# testboard.net
KiCad netlist of a schematic drawn in Altium Designer
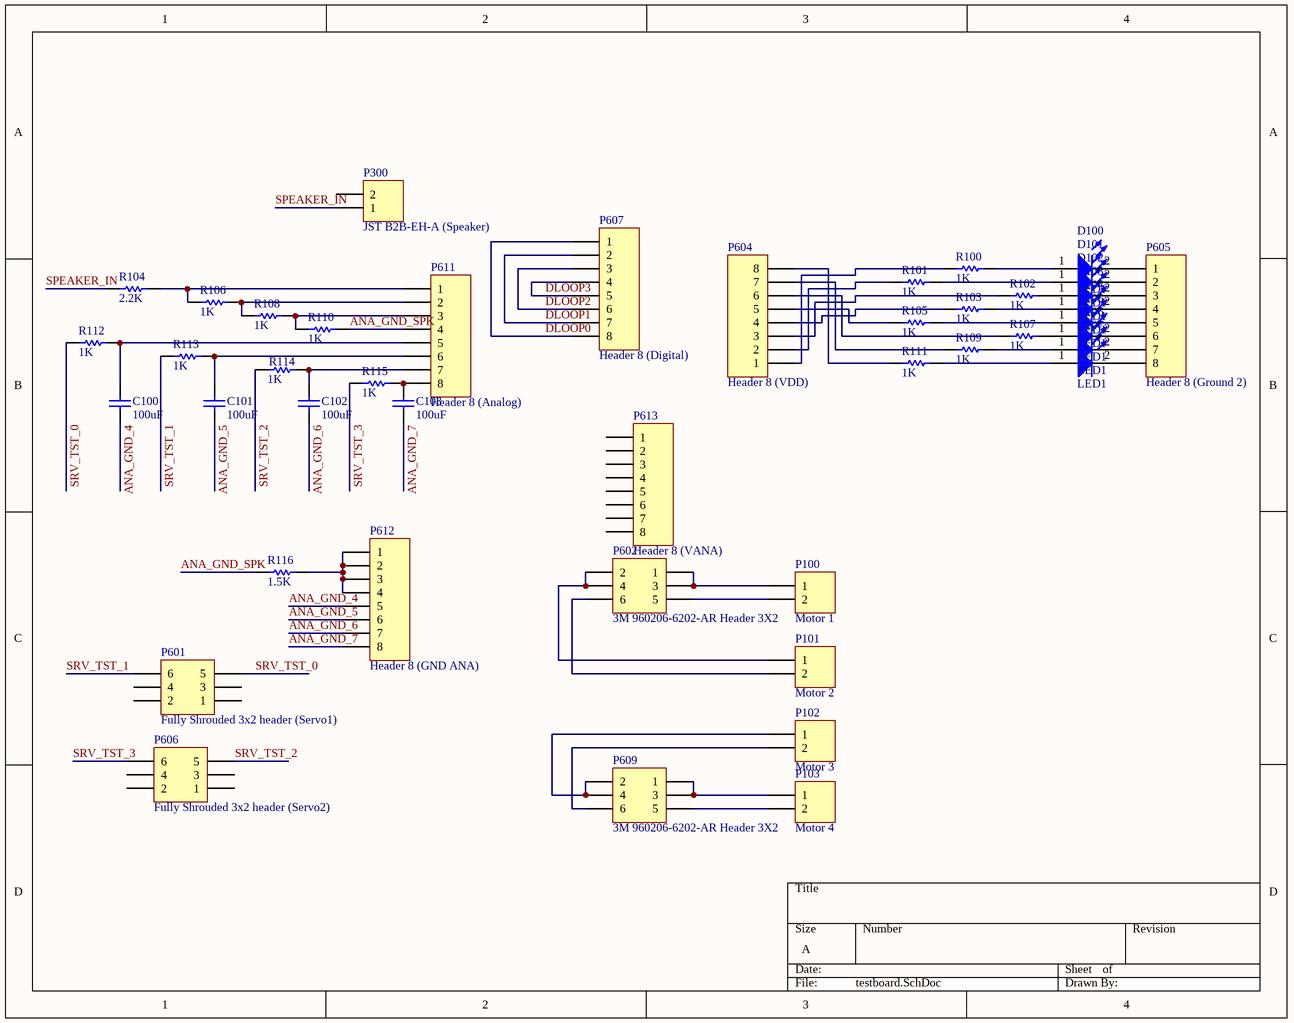
[diagram p0: testboard.SchDoc]

(export (version "E")
  (design (tool "Eeschema 10.0.6"))
  (components
    (comp (ref "C100")
      (value "100uF")
      (footprint "CAPPR5-5x5")
      (description "Capacitor")
      (fields (field (name "PUBLISHER") "Altium Limited"))
      (libsource (lib "Miscellaneous Devices") (part "Cap"))
    )
    (comp (ref "C101")
      (value "100uF")
      (footprint "CAPPR5-5x5")
      (description "Capacitor")
      (fields (field (name "PUBLISHER") "Altium Limited"))
      (libsource (lib "Miscellaneous Devices") (part "Cap"))
    )
    (comp (ref "C102")
      (value "100uF")
      (footprint "CAPPR5-5x5")
      (description "Capacitor")
      (fields (field (name "PUBLISHER") "Altium Limited"))
      (libsource (lib "Miscellaneous Devices") (part "Cap"))
    )
    (comp (ref "C103")
      (value "100uF")
      (footprint "CAPPR5-5x5")
      (description "Capacitor")
      (fields (field (name "PUBLISHER") "Altium Limited"))
      (libsource (lib "Miscellaneous Devices") (part "Cap"))
    )
    (comp (ref "D100")
      (value "LED1")
      (footprint "TLHG520")
      (description "Typical RED GaAs LED")
      (fields (field (name "PUBLISHER") "Altium Limited"))
      (libsource (lib "Miscellaneous Devices") (part "LED1"))
    )
    (comp (ref "D101")
      (value "LED1")
      (footprint "TLHG520")
      (description "Typical RED GaAs LED")
      (fields (field (name "PUBLISHER") "Altium Limited"))
      (libsource (lib "Miscellaneous Devices") (part "LED1"))
    )
    (comp (ref "D102")
      (value "LED1")
      (footprint "TLHG520")
      (description "Typical RED GaAs LED")
      (fields (field (name "PUBLISHER") "Altium Limited"))
      (libsource (lib "Miscellaneous Devices") (part "LED1"))
    )
    (comp (ref "D103")
      (value "LED1")
      (footprint "TLHG520")
      (description "Typical RED GaAs LED")
      (fields (field (name "PUBLISHER") "Altium Limited"))
      (libsource (lib "Miscellaneous Devices") (part "LED1"))
    )
    (comp (ref "D104")
      (value "LED1")
      (footprint "TLHG520")
      (description "Typical RED GaAs LED")
      (fields (field (name "PUBLISHER") "Altium Limited"))
      (libsource (lib "") (part "LED1_1"))
    )
    (comp (ref "D105")
      (value "LED1")
      (footprint "TLHG520")
      (description "Typical RED GaAs LED")
      (fields (field (name "PUBLISHER") "Altium Limited"))
      (libsource (lib "Miscellaneous Devices") (part "LED1"))
    )
    (comp (ref "D106")
      (value "LED1")
      (footprint "TLHG520")
      (description "Typical RED GaAs LED")
      (fields (field (name "PUBLISHER") "Altium Limited"))
      (libsource (lib "Miscellaneous Devices") (part "LED1"))
    )
    (comp (ref "D107")
      (value "LED1")
      (footprint "TLHG520")
      (description "Typical RED GaAs LED")
      (fields (field (name "PUBLISHER") "Altium Limited"))
      (libsource (lib "Miscellaneous Devices") (part "LED1"))
    )
    (comp (ref "P100")
      (value "Motor 1")
      (footprint "weidmuller_1716060000")
      (description "Header, 2-Pin")
      (fields (field (name "PUBLISHER") "Altium Limited"))
      (libsource (lib "") (part "Header 2_1"))
    )
    (comp (ref "P101")
      (value "Motor 2")
      (footprint "weidmuller_1716060000")
      (description "Header, 2-Pin")
      (fields (field (name "PUBLISHER") "Altium Limited"))
      (libsource (lib "") (part "Header 2_1"))
    )
    (comp (ref "P102")
      (value "Motor 3")
      (footprint "weidmuller_1716060000")
      (description "Header, 2-Pin")
      (fields (field (name "PUBLISHER") "Altium Limited"))
      (libsource (lib "") (part "Header 2_1"))
    )
    (comp (ref "P103")
      (value "Motor 4")
      (footprint "weidmuller_1716060000")
      (description "Header, 2-Pin")
      (fields (field (name "PUBLISHER") "Altium Limited"))
      (libsource (lib "") (part "Header 2_1"))
    )
    (comp (ref "P300")
      (value "JST B2B-EH-A (Speaker)")
      (footprint "JST_B2B_EH_A")
      (description "Header, 2-Pin")
      (fields (field (name "PUBLISHER") "Altium Limited"))
      (libsource (lib "Miscellaneous Connectors") (part "Header 2"))
    )
    (comp (ref "P601")
      (value "Fully Shrouded 3x2 header (Servo1)")
      (footprint "HEADER2X3_SHROUDED")
      (description "Header, 3-Pin, Dual row")
      (fields (field (name "PUBLISHER") "Altium Limited"))
      (libsource (lib "") (part "Header 3X2_1"))
    )
    (comp (ref "P602")
      (value "3M 960206-6202-AR Header 3X2")
      (footprint "HDR2X3")
      (description "Header, 3-Pin, Dual row")
      (fields (field (name "PUBLISHER") "Altium Limited"))
      (libsource (lib "Miscellaneous Connectors") (part "Header 3X2"))
    )
    (comp (ref "P604")
      (value "Header 8 (VDD)")
      (footprint "HDR1X8")
      (description "Header, 8-Pin")
      (fields (field (name "PUBLISHER") "Altium Limited"))
      (libsource (lib "") (part "Header 8_1"))
    )
    (comp (ref "P605")
      (value "Header 8 (Ground 2)")
      (footprint "HDR1X8")
      (description "Header, 8-Pin")
      (fields (field (name "PUBLISHER") "Altium Limited"))
      (libsource (lib "Miscellaneous Connectors") (part "Header 8"))
    )
    (comp (ref "P606")
      (value "Fully Shrouded 3x2 header (Servo2)")
      (footprint "HEADER2X3_SHROUDED")
      (description "Header, 3-Pin, Dual row")
      (fields (field (name "PUBLISHER") "Altium Limited"))
      (libsource (lib "") (part "Header 3X2_1"))
    )
    (comp (ref "P607")
      (value "Header 8 (Digital)")
      (footprint "HDR1X8")
      (description "Header, 8-Pin")
      (fields (field (name "PUBLISHER") "Altium Limited"))
      (libsource (lib "Miscellaneous Connectors") (part "Header 8"))
    )
    (comp (ref "P609")
      (value "3M 960206-6202-AR Header 3X2")
      (footprint "HDR2X3")
      (description "Header, 3-Pin, Dual row")
      (fields (field (name "PUBLISHER") "Altium Limited"))
      (libsource (lib "Miscellaneous Connectors") (part "Header 3X2"))
    )
    (comp (ref "P611")
      (value "Header 8 (Analog)")
      (footprint "HDR1X8")
      (description "Header, 8-Pin")
      (fields (field (name "PUBLISHER") "Altium Limited"))
      (libsource (lib "Miscellaneous Connectors") (part "Header 8"))
    )
    (comp (ref "P612")
      (value "Header 8 (GND ANA)")
      (footprint "HDR1X8")
      (description "Header, 8-Pin")
      (fields (field (name "PUBLISHER") "Altium Limited"))
      (libsource (lib "Miscellaneous Connectors") (part "Header 8"))
    )
    (comp (ref "P613")
      (value "Header 8 (VANA)")
      (footprint "HDR1X8")
      (description "Header, 8-Pin")
      (fields (field (name "PUBLISHER") "Altium Limited"))
      (libsource (lib "Miscellaneous Connectors") (part "Header 8"))
    )
    (comp (ref "R100")
      (value "1K")
      (footprint "AXIAL-0.3")
      (description "Resistor")
      (fields (field (name "PUBLISHER") "Altium Limited"))
      (libsource (lib "Miscellaneous Devices") (part "Res1"))
    )
    (comp (ref "R101")
      (value "1K")
      (footprint "AXIAL-0.3")
      (description "Resistor")
      (fields (field (name "PUBLISHER") "Altium Limited"))
      (libsource (lib "Miscellaneous Devices") (part "Res1"))
    )
    (comp (ref "R102")
      (value "1K")
      (footprint "AXIAL-0.3")
      (description "Resistor")
      (fields (field (name "PUBLISHER") "Altium Limited"))
      (libsource (lib "Miscellaneous Devices") (part "Res1"))
    )
    (comp (ref "R103")
      (value "1K")
      (footprint "AXIAL-0.3")
      (description "Resistor")
      (fields (field (name "PUBLISHER") "Altium Limited"))
      (libsource (lib "Miscellaneous Devices") (part "Res1"))
    )
    (comp (ref "R104")
      (value "2.2K")
      (footprint "AXIAL-0.3")
      (description "Resistor")
      (fields (field (name "PUBLISHER") "Altium Limited"))
      (libsource (lib "Miscellaneous Devices") (part "Res1"))
    )
    (comp (ref "R105")
      (value "1K")
      (footprint "AXIAL-0.3")
      (description "Resistor")
      (fields (field (name "PUBLISHER") "Altium Limited"))
      (libsource (lib "Miscellaneous Devices") (part "Res1"))
    )
    (comp (ref "R106")
      (value "1K")
      (footprint "AXIAL-0.3")
      (description "Resistor")
      (fields (field (name "PUBLISHER") "Altium Limited"))
      (libsource (lib "Miscellaneous Devices") (part "Res1"))
    )
    (comp (ref "R107")
      (value "1K")
      (footprint "AXIAL-0.3")
      (description "Resistor")
      (fields (field (name "PUBLISHER") "Altium Limited"))
      (libsource (lib "Miscellaneous Devices") (part "Res1"))
    )
    (comp (ref "R108")
      (value "1K")
      (footprint "AXIAL-0.3")
      (description "Resistor")
      (fields (field (name "PUBLISHER") "Altium Limited"))
      (libsource (lib "Miscellaneous Devices") (part "Res1"))
    )
    (comp (ref "R109")
      (value "1K")
      (footprint "AXIAL-0.3")
      (description "Resistor")
      (fields (field (name "PUBLISHER") "Altium Limited"))
      (libsource (lib "Miscellaneous Devices") (part "Res1"))
    )
    (comp (ref "R110")
      (value "1K")
      (footprint "AXIAL-0.3")
      (description "Resistor")
      (fields (field (name "PUBLISHER") "Altium Limited"))
      (libsource (lib "Miscellaneous Devices") (part "Res1"))
    )
    (comp (ref "R111")
      (value "1K")
      (footprint "AXIAL-0.3")
      (description "Resistor")
      (fields (field (name "PUBLISHER") "Altium Limited"))
      (libsource (lib "Miscellaneous Devices") (part "Res1"))
    )
    (comp (ref "R112")
      (value "1K")
      (footprint "AXIAL-0.3")
      (description "Resistor")
      (fields (field (name "PUBLISHER") "Altium Limited"))
      (libsource (lib "Miscellaneous Devices") (part "Res1"))
    )
    (comp (ref "R113")
      (value "1K")
      (footprint "AXIAL-0.3")
      (description "Resistor")
      (fields (field (name "PUBLISHER") "Altium Limited"))
      (libsource (lib "Miscellaneous Devices") (part "Res1"))
    )
    (comp (ref "R114")
      (value "1K")
      (footprint "AXIAL-0.3")
      (description "Resistor")
      (fields (field (name "PUBLISHER") "Altium Limited"))
      (libsource (lib "Miscellaneous Devices") (part "Res1"))
    )
    (comp (ref "R115")
      (value "1K")
      (footprint "AXIAL-0.3")
      (description "Resistor")
      (fields (field (name "PUBLISHER") "Altium Limited"))
      (libsource (lib "Miscellaneous Devices") (part "Res1"))
    )
    (comp (ref "R116")
      (value "1.5K")
      (footprint "AXIAL-0.3")
      (description "Resistor")
      (fields (field (name "PUBLISHER") "Altium Limited"))
      (libsource (lib "Miscellaneous Devices") (part "Res1"))
    )
  )
  (nets
    (net (code "1") (name "/ANA_GND_4") (class "Default")
      (node (ref "C100") (pin "1") (pinfunction "1_1") (pintype "passive"))
      (node (ref "P612") (pin "5") (pinfunction "5_5") (pintype "passive"))
    )
    (net (code "2") (name "/ANA_GND_5") (class "Default")
      (node (ref "C101") (pin "1") (pinfunction "1_1") (pintype "passive"))
      (node (ref "P612") (pin "6") (pinfunction "6_6") (pintype "passive"))
    )
    (net (code "3") (name "/ANA_GND_6") (class "Default")
      (node (ref "C102") (pin "1") (pinfunction "1_1") (pintype "passive"))
      (node (ref "P612") (pin "7") (pinfunction "7_7") (pintype "passive"))
    )
    (net (code "4") (name "/ANA_GND_7") (class "Default")
      (node (ref "C103") (pin "1") (pinfunction "1_1") (pintype "passive"))
      (node (ref "P612") (pin "8") (pinfunction "8_8") (pintype "passive"))
    )
    (net (code "5") (name "/ANA_GND_SPK") (class "Default")
      (node (ref "P611") (pin "4") (pinfunction "4_4") (pintype "passive"))
      (node (ref "R110") (pin "1") (pinfunction "1_1") (pintype "passive"))
      (node (ref "R116") (pin "1") (pinfunction "1_1") (pintype "passive"))
    )
    (net (code "6") (name "/DLOOP0") (class "Default")
      (node (ref "P607") (pin "1") (pinfunction "1_1") (pintype "passive"))
      (node (ref "P607") (pin "8") (pinfunction "8_8") (pintype "passive"))
    )
    (net (code "7") (name "/DLOOP1") (class "Default")
      (node (ref "P607") (pin "2") (pinfunction "2_2") (pintype "passive"))
      (node (ref "P607") (pin "7") (pinfunction "7_7") (pintype "passive"))
    )
    (net (code "8") (name "/DLOOP2") (class "Default")
      (node (ref "P607") (pin "3") (pinfunction "3_3") (pintype "passive"))
      (node (ref "P607") (pin "6") (pinfunction "6_6") (pintype "passive"))
    )
    (net (code "9") (name "/DLOOP3") (class "Default")
      (node (ref "P607") (pin "4") (pinfunction "4_4") (pintype "passive"))
      (node (ref "P607") (pin "5") (pinfunction "5_5") (pintype "passive"))
    )
    (net (code "10") (name "/SPEAKER_IN") (class "Default")
      (node (ref "P300") (pin "1") (pinfunction "1_1") (pintype "passive"))
      (node (ref "R104") (pin "2") (pinfunction "2_2") (pintype "passive"))
    )
    (net (code "11") (name "/SRV_TST_0") (class "Default")
      (node (ref "P601") (pin "5") (pinfunction "5_5") (pintype "passive"))
      (node (ref "R112") (pin "1") (pinfunction "1_1") (pintype "passive"))
    )
    (net (code "12") (name "/SRV_TST_1") (class "Default")
      (node (ref "P601") (pin "6") (pinfunction "6_6") (pintype "passive"))
      (node (ref "R113") (pin "1") (pinfunction "1_1") (pintype "passive"))
    )
    (net (code "13") (name "/SRV_TST_2") (class "Default")
      (node (ref "P606") (pin "5") (pinfunction "5_5") (pintype "passive"))
      (node (ref "R114") (pin "1") (pinfunction "1_1") (pintype "passive"))
    )
    (net (code "14") (name "/SRV_TST_3") (class "Default")
      (node (ref "P606") (pin "6") (pinfunction "6_6") (pintype "passive"))
      (node (ref "R115") (pin "1") (pinfunction "1_1") (pintype "passive"))
    )
    (net (code "15") (name "Net-(C100-Pad2)") (class "Default")
      (node (ref "C100") (pin "2") (pinfunction "2_2") (pintype "passive"))
      (node (ref "P611") (pin "5") (pinfunction "5_5") (pintype "passive"))
      (node (ref "R112") (pin "2") (pinfunction "2_2") (pintype "passive"))
    )
    (net (code "16") (name "Net-(C101-Pad2)") (class "Default")
      (node (ref "C101") (pin "2") (pinfunction "2_2") (pintype "passive"))
      (node (ref "P611") (pin "6") (pinfunction "6_6") (pintype "passive"))
      (node (ref "R113") (pin "2") (pinfunction "2_2") (pintype "passive"))
    )
    (net (code "17") (name "Net-(C102-Pad2)") (class "Default")
      (node (ref "C102") (pin "2") (pinfunction "2_2") (pintype "passive"))
      (node (ref "P611") (pin "7") (pinfunction "7_7") (pintype "passive"))
      (node (ref "R114") (pin "2") (pinfunction "2_2") (pintype "passive"))
    )
    (net (code "18") (name "Net-(C103-Pad2)") (class "Default")
      (node (ref "C103") (pin "2") (pinfunction "2_2") (pintype "passive"))
      (node (ref "P611") (pin "8") (pinfunction "8_8") (pintype "passive"))
      (node (ref "R115") (pin "2") (pinfunction "2_2") (pintype "passive"))
    )
    (net (code "19") (name "Net-(D100-A)") (class "Default")
      (node (ref "D100") (pin "1") (pinfunction "A_1") (pintype "passive"))
      (node (ref "R100") (pin "1") (pinfunction "1_1") (pintype "passive"))
    )
    (net (code "20") (name "Net-(D100-K)") (class "Default")
      (node (ref "D100") (pin "2") (pinfunction "K_2") (pintype "passive"))
      (node (ref "P605") (pin "1") (pinfunction "1_1") (pintype "passive"))
    )
    (net (code "21") (name "Net-(D101-A)") (class "Default")
      (node (ref "D101") (pin "1") (pinfunction "A_1") (pintype "passive"))
      (node (ref "R101") (pin "1") (pinfunction "1_1") (pintype "passive"))
    )
    (net (code "22") (name "Net-(D101-K)") (class "Default")
      (node (ref "D101") (pin "2") (pinfunction "K_2") (pintype "passive"))
      (node (ref "P605") (pin "2") (pinfunction "2_2") (pintype "passive"))
    )
    (net (code "23") (name "Net-(D102-A)") (class "Default")
      (node (ref "D102") (pin "1") (pinfunction "A_1") (pintype "passive"))
      (node (ref "R102") (pin "1") (pinfunction "1_1") (pintype "passive"))
    )
    (net (code "24") (name "Net-(D102-K)") (class "Default")
      (node (ref "D102") (pin "2") (pinfunction "K_2") (pintype "passive"))
      (node (ref "P605") (pin "3") (pinfunction "3_3") (pintype "passive"))
    )
    (net (code "25") (name "Net-(D103-A)") (class "Default")
      (node (ref "D103") (pin "1") (pinfunction "A_1") (pintype "passive"))
      (node (ref "R103") (pin "1") (pinfunction "1_1") (pintype "passive"))
    )
    (net (code "26") (name "Net-(D103-K)") (class "Default")
      (node (ref "D103") (pin "2") (pinfunction "K_2") (pintype "passive"))
      (node (ref "P605") (pin "4") (pinfunction "4_4") (pintype "passive"))
    )
    (net (code "27") (name "Net-(D104A-A)") (class "Default")
      (node (ref "D104") (pin "1") (pinfunction "A_1") (pintype "passive"))
      (node (ref "R105") (pin "1") (pinfunction "1_1") (pintype "passive"))
    )
    (net (code "28") (name "Net-(D105-A)") (class "Default")
      (node (ref "D105") (pin "1") (pinfunction "A_1") (pintype "passive"))
      (node (ref "R107") (pin "1") (pinfunction "1_1") (pintype "passive"))
    )
    (net (code "29") (name "Net-(D105-K)") (class "Default")
      (node (ref "D105") (pin "2") (pinfunction "K_2") (pintype "passive"))
      (node (ref "P605") (pin "6") (pinfunction "6_6") (pintype "passive"))
    )
    (net (code "30") (name "Net-(D106-A)") (class "Default")
      (node (ref "D106") (pin "1") (pinfunction "A_1") (pintype "passive"))
      (node (ref "R109") (pin "1") (pinfunction "1_1") (pintype "passive"))
    )
    (net (code "31") (name "Net-(D106-K)") (class "Default")
      (node (ref "D106") (pin "2") (pinfunction "K_2") (pintype "passive"))
      (node (ref "P605") (pin "7") (pinfunction "7_7") (pintype "passive"))
    )
    (net (code "32") (name "Net-(D107-A)") (class "Default")
      (node (ref "D107") (pin "1") (pinfunction "A_1") (pintype "passive"))
      (node (ref "R111") (pin "1") (pinfunction "1_1") (pintype "passive"))
    )
    (net (code "33") (name "Net-(D107-K)") (class "Default")
      (node (ref "D107") (pin "2") (pinfunction "K_2") (pintype "passive"))
      (node (ref "P605") (pin "8") (pinfunction "8_8") (pintype "passive"))
    )
    (net (code "34") (name "Net-(P100-Pad1)") (class "Default")
      (node (ref "P100") (pin "1") (pinfunction "1_1") (pintype "passive"))
      (node (ref "P602") (pin "1") (pinfunction "1_1") (pintype "passive"))
      (node (ref "P602") (pin "3") (pinfunction "3_3") (pintype "passive"))
    )
    (net (code "35") (name "Net-(P100-Pad2)") (class "Default")
      (node (ref "P100") (pin "2") (pinfunction "2_2") (pintype "passive"))
      (node (ref "P602") (pin "5") (pinfunction "5_5") (pintype "passive"))
    )
    (net (code "36") (name "Net-(P101-Pad1)") (class "Default")
      (node (ref "P101") (pin "1") (pinfunction "1_1") (pintype "passive"))
      (node (ref "P602") (pin "2") (pinfunction "2_2") (pintype "passive"))
      (node (ref "P602") (pin "4") (pinfunction "4_4") (pintype "passive"))
    )
    (net (code "37") (name "Net-(P101-Pad2)") (class "Default")
      (node (ref "P101") (pin "2") (pinfunction "2_2") (pintype "passive"))
      (node (ref "P602") (pin "6") (pinfunction "6_6") (pintype "passive"))
    )
    (net (code "38") (name "Net-(P102-Pad1)") (class "Default")
      (node (ref "P102") (pin "1") (pinfunction "1_1") (pintype "passive"))
      (node (ref "P609") (pin "2") (pinfunction "2_2") (pintype "passive"))
      (node (ref "P609") (pin "4") (pinfunction "4_4") (pintype "passive"))
    )
    (net (code "39") (name "Net-(P102-Pad2)") (class "Default")
      (node (ref "P102") (pin "2") (pinfunction "2_2") (pintype "passive"))
      (node (ref "P609") (pin "6") (pinfunction "6_6") (pintype "passive"))
    )
    (net (code "40") (name "Net-(P103-Pad1)") (class "Default")
      (node (ref "P103") (pin "1") (pinfunction "1_1") (pintype "passive"))
      (node (ref "P609") (pin "1") (pinfunction "1_1") (pintype "passive"))
      (node (ref "P609") (pin "3") (pinfunction "3_3") (pintype "passive"))
    )
    (net (code "41") (name "Net-(P103-Pad2)") (class "Default")
      (node (ref "P103") (pin "2") (pinfunction "2_2") (pintype "passive"))
      (node (ref "P609") (pin "5") (pinfunction "5_5") (pintype "passive"))
    )
    (net (code "42") (name "Net-(P604-Pad1)") (class "Default")
      (node (ref "P604") (pin "1") (pinfunction "1_1") (pintype "passive"))
      (node (ref "R100") (pin "2") (pinfunction "2_2") (pintype "passive"))
    )
    (net (code "43") (name "Net-(P604-Pad2)") (class "Default")
      (node (ref "P604") (pin "2") (pinfunction "2_2") (pintype "passive"))
      (node (ref "R101") (pin "2") (pinfunction "2_2") (pintype "passive"))
    )
    (net (code "44") (name "Net-(P604-Pad3)") (class "Default")
      (node (ref "P604") (pin "3") (pinfunction "3_3") (pintype "passive"))
      (node (ref "R102") (pin "2") (pinfunction "2_2") (pintype "passive"))
    )
    (net (code "45") (name "Net-(P604-Pad4)") (class "Default")
      (node (ref "P604") (pin "4") (pinfunction "4_4") (pintype "passive"))
      (node (ref "R103") (pin "2") (pinfunction "2_2") (pintype "passive"))
    )
    (net (code "46") (name "Net-(P604-Pad5)") (class "Default")
      (node (ref "P604") (pin "5") (pinfunction "5_5") (pintype "passive"))
      (node (ref "R105") (pin "2") (pinfunction "2_2") (pintype "passive"))
    )
    (net (code "47") (name "Net-(P604-Pad6)") (class "Default")
      (node (ref "P604") (pin "6") (pinfunction "6_6") (pintype "passive"))
      (node (ref "R107") (pin "2") (pinfunction "2_2") (pintype "passive"))
    )
    (net (code "48") (name "Net-(P604-Pad7)") (class "Default")
      (node (ref "P604") (pin "7") (pinfunction "7_7") (pintype "passive"))
      (node (ref "R109") (pin "2") (pinfunction "2_2") (pintype "passive"))
    )
    (net (code "49") (name "Net-(P604-Pad8)") (class "Default")
      (node (ref "P604") (pin "8") (pinfunction "8_8") (pintype "passive"))
      (node (ref "R111") (pin "2") (pinfunction "2_2") (pintype "passive"))
    )
    (net (code "50") (name "Net-(P611-Pad1)") (class "Default")
      (node (ref "P611") (pin "1") (pinfunction "1_1") (pintype "passive"))
      (node (ref "R104") (pin "1") (pinfunction "1_1") (pintype "passive"))
      (node (ref "R106") (pin "2") (pinfunction "2_2") (pintype "passive"))
    )
    (net (code "51") (name "Net-(P611-Pad2)") (class "Default")
      (node (ref "P611") (pin "2") (pinfunction "2_2") (pintype "passive"))
      (node (ref "R106") (pin "1") (pinfunction "1_1") (pintype "passive"))
      (node (ref "R108") (pin "2") (pinfunction "2_2") (pintype "passive"))
    )
    (net (code "52") (name "Net-(P611-Pad3)") (class "Default")
      (node (ref "P611") (pin "3") (pinfunction "3_3") (pintype "passive"))
      (node (ref "R108") (pin "1") (pinfunction "1_1") (pintype "passive"))
      (node (ref "R110") (pin "2") (pinfunction "2_2") (pintype "passive"))
    )
    (net (code "53") (name "Net-(P612-Pad1)") (class "Default")
      (node (ref "P612") (pin "1") (pinfunction "1_1") (pintype "passive"))
      (node (ref "P612") (pin "2") (pinfunction "2_2") (pintype "passive"))
      (node (ref "P612") (pin "3") (pinfunction "3_3") (pintype "passive"))
      (node (ref "P612") (pin "4") (pinfunction "4_4") (pintype "passive"))
      (node (ref "R116") (pin "2") (pinfunction "2_2") (pintype "passive"))
    )
    (net (code "54") (name "unconnected-(P300-Pad2)") (class "Default")
      (node (ref "P300") (pin "2") (pinfunction "2_2") (pintype "passive"))
    )
    (net (code "55") (name "unconnected-(P601-Pad1)") (class "Default")
      (node (ref "P601") (pin "1") (pinfunction "1_1") (pintype "passive"))
    )
    (net (code "56") (name "unconnected-(P601-Pad2)") (class "Default")
      (node (ref "P601") (pin "2") (pinfunction "2_2") (pintype "passive"))
    )
    (net (code "57") (name "unconnected-(P601-Pad3)") (class "Default")
      (node (ref "P601") (pin "3") (pinfunction "3_3") (pintype "passive"))
    )
    (net (code "58") (name "unconnected-(P601-Pad4)") (class "Default")
      (node (ref "P601") (pin "4") (pinfunction "4_4") (pintype "passive"))
    )
    (net (code "59") (name "unconnected-(P605-Pad5)") (class "Default")
      (node (ref "P605") (pin "5") (pinfunction "5_5") (pintype "passive"))
    )
    (net (code "60") (name "unconnected-(P606-Pad1)") (class "Default")
      (node (ref "P606") (pin "1") (pinfunction "1_1") (pintype "passive"))
    )
    (net (code "61") (name "unconnected-(P606-Pad2)") (class "Default")
      (node (ref "P606") (pin "2") (pinfunction "2_2") (pintype "passive"))
    )
    (net (code "62") (name "unconnected-(P606-Pad3)") (class "Default")
      (node (ref "P606") (pin "3") (pinfunction "3_3") (pintype "passive"))
    )
    (net (code "63") (name "unconnected-(P606-Pad4)") (class "Default")
      (node (ref "P606") (pin "4") (pinfunction "4_4") (pintype "passive"))
    )
    (net (code "64") (name "unconnected-(P613-Pad1)") (class "Default")
      (node (ref "P613") (pin "1") (pinfunction "1_1") (pintype "passive"))
    )
    (net (code "65") (name "unconnected-(P613-Pad2)") (class "Default")
      (node (ref "P613") (pin "2") (pinfunction "2_2") (pintype "passive"))
    )
    (net (code "66") (name "unconnected-(P613-Pad3)") (class "Default")
      (node (ref "P613") (pin "3") (pinfunction "3_3") (pintype "passive"))
    )
    (net (code "67") (name "unconnected-(P613-Pad4)") (class "Default")
      (node (ref "P613") (pin "4") (pinfunction "4_4") (pintype "passive"))
    )
    (net (code "68") (name "unconnected-(P613-Pad5)") (class "Default")
      (node (ref "P613") (pin "5") (pinfunction "5_5") (pintype "passive"))
    )
    (net (code "69") (name "unconnected-(P613-Pad6)") (class "Default")
      (node (ref "P613") (pin "6") (pinfunction "6_6") (pintype "passive"))
    )
    (net (code "70") (name "unconnected-(P613-Pad7)") (class "Default")
      (node (ref "P613") (pin "7") (pinfunction "7_7") (pintype "passive"))
    )
    (net (code "71") (name "unconnected-(P613-Pad8)") (class "Default")
      (node (ref "P613") (pin "8") (pinfunction "8_8") (pintype "passive"))
    )
  )
)
